# V5_9aSMD.net
KiCad netlist of a schematic drawn in EAGLE
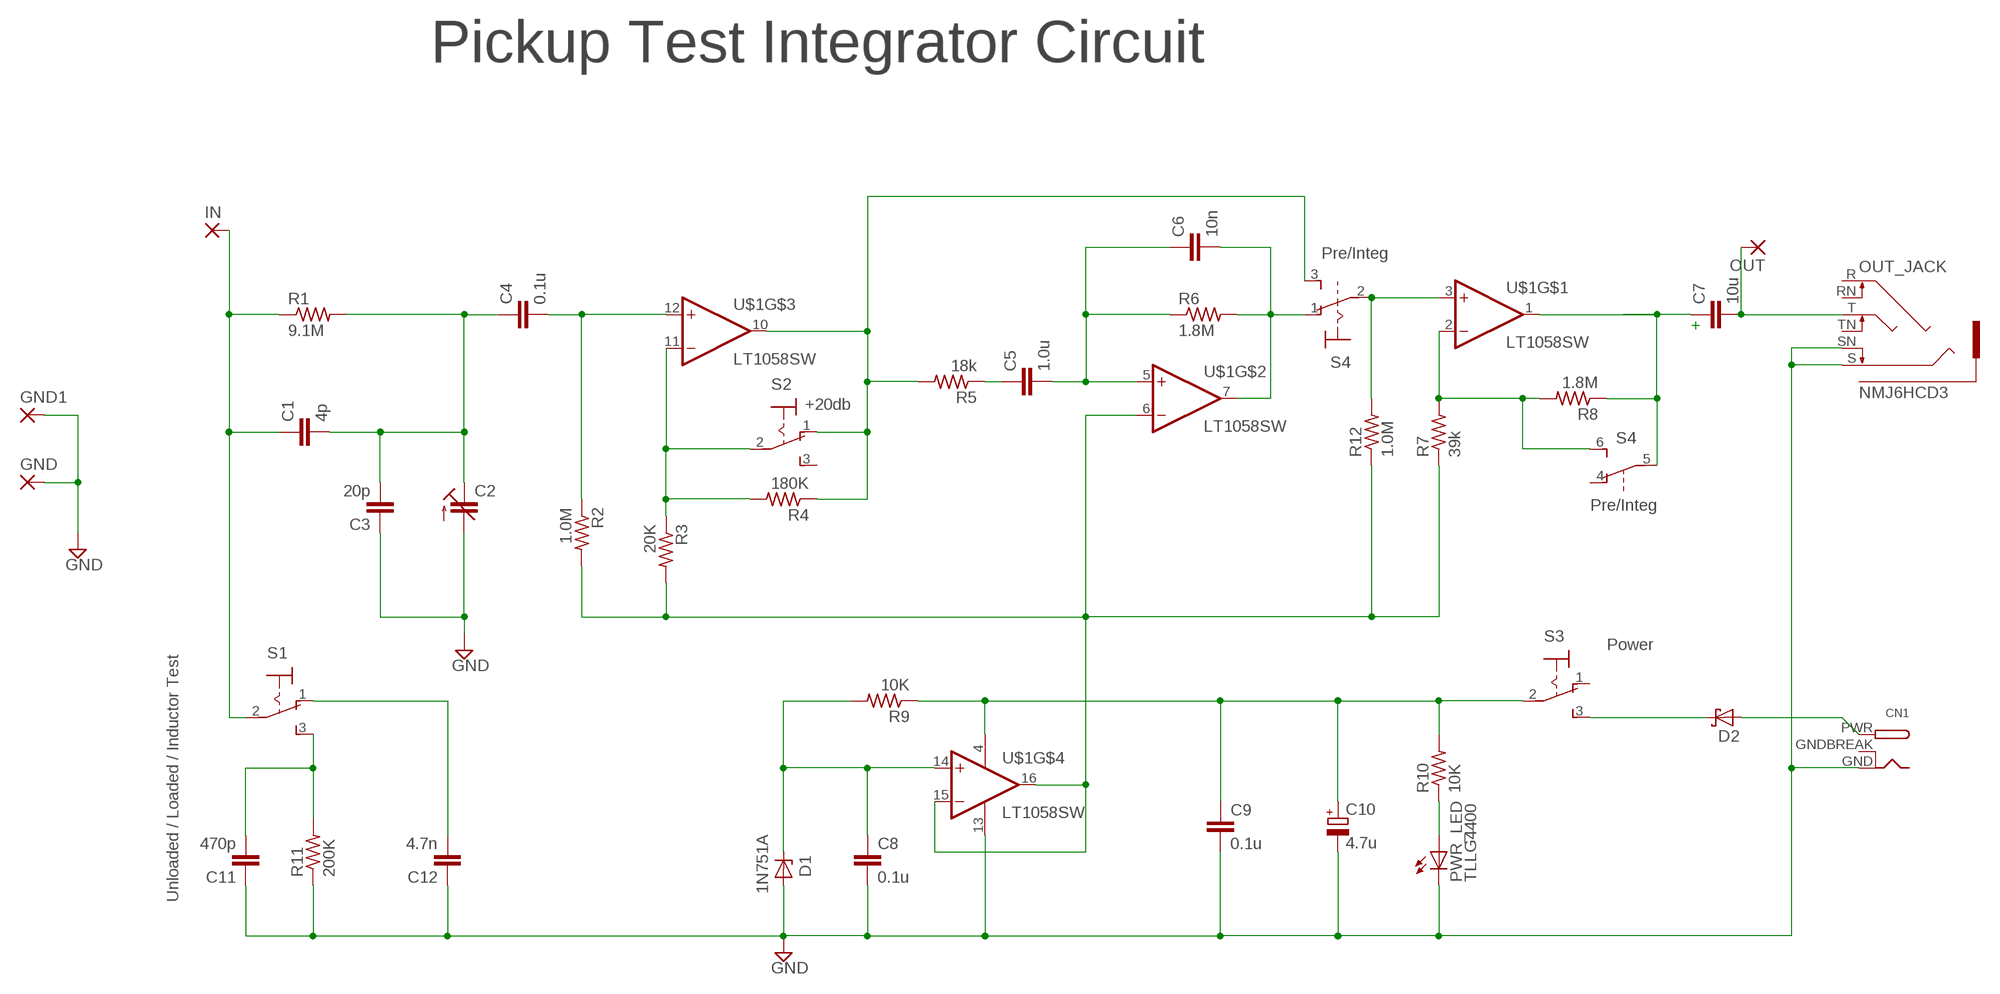
[diagram p0: schematic, sheet 1]

(export (version "E")
  (design (tool "Eeschema 10.0.6"))
  (components
    (comp (ref "C1")
      (value "4p")
      (footprint "eagle-import:C0805")
      (libsource (lib "eagle-import") (part "C-EUC0805"))
    )
    (comp (ref "C2")
      (value "C-TRIMMGKG20015")
      (footprint "eagle-import:GKG20015")
      (libsource (lib "eagle-import") (part "C-TRIMMGKG20015"))
    )
    (comp (ref "C3")
      (value "20p")
      (footprint "eagle-import:C0805")
      (libsource (lib "eagle-import") (part "C-EUC0805"))
    )
    (comp (ref "C4")
      (value "0.1u")
      (footprint "eagle-import:C0805")
      (libsource (lib "eagle-import") (part "C-EUC0805"))
    )
    (comp (ref "C5")
      (value "1.0u")
      (footprint "eagle-import:C0805")
      (libsource (lib "eagle-import") (part "C-EUC0805"))
    )
    (comp (ref "C6")
      (value "10n")
      (footprint "eagle-import:C0805")
      (libsource (lib "eagle-import") (part "C-EUC0805"))
    )
    (comp (ref "C7")
      (value "10u")
      (footprint "eagle-import:C1206K")
      (libsource (lib "eagle-import") (part "C-EUC1206K"))
    )
    (comp (ref "C8")
      (value "0.1u")
      (footprint "eagle-import:C0805")
      (libsource (lib "eagle-import") (part "C-EUC0805"))
    )
    (comp (ref "C9")
      (value "0.1u")
      (footprint "eagle-import:C0805")
      (libsource (lib "eagle-import") (part "C-EUC0805"))
    )
    (comp (ref "C10")
      (value "4.7u")
      (footprint "eagle-import:A_3216-18R")
      (libsource (lib "eagle-import") (part "CPOL-EUA/3216-18R"))
    )
    (comp (ref "C11")
      (value "470p")
      (footprint "eagle-import:C0805")
      (libsource (lib "eagle-import") (part "C-EUC0805"))
    )
    (comp (ref "C12")
      (value "4.7n")
      (footprint "eagle-import:C0805")
      (libsource (lib "eagle-import") (part "C-EUC0805"))
    )
    (comp (ref "CN1")
      (value "DCBARRELPTH")
      (footprint "eagle-import:DCJACK_2MM_PTH")
      (libsource (lib "eagle-import") (part "DCBARRELPTH"))
    )
    (comp (ref "D1")
      (value "ZENER-DIODESOD80C")
      (footprint "eagle-import:SOD80C")
      (libsource (lib "eagle-import") (part "ZENER-DIODESOD80C"))
    )
    (comp (ref "D2")
      (value "SCHOTTKY-DIODESMD")
      (footprint "eagle-import:SMB")
      (libsource (lib "eagle-import") (part "SCHOTTKY-DIODESMD"))
    )
    (comp (ref "GND")
      (value "2,54/1,1")
      (footprint "eagle-import:2,54_1,1")
      (libsource (lib "eagle-import") (part "2,54/1,1"))
    )
    (comp (ref "GND1")
      (value "2,54/1,1")
      (footprint "eagle-import:2,54_1,1")
      (libsource (lib "eagle-import") (part "2,54/1,1"))
    )
    (comp (ref "IN")
      (value "2,54/1,1")
      (footprint "eagle-import:2,54_1,1")
      (libsource (lib "eagle-import") (part "2,54/1,1"))
    )
    (comp (ref "OUT")
      (value "2,54/1,1")
      (footprint "eagle-import:2,54_1,1")
      (libsource (lib "eagle-import") (part "2,54/1,1"))
    )
    (comp (ref "OUT_JACK")
      (value "NMJ6HCD3")
      (footprint "eagle-import:AUDIO_JACK_NEUTRIK")
      (libsource (lib "eagle-import") (part "NMJ6HCD3"))
    )
    (comp (ref "PWR_LED")
      (value "TLLG4400")
      (footprint "eagle-import:LED3MM")
      (fields (field (name "MF") "VISHAY SEMICONDUCTOR"))
      (libsource (lib "eagle-import") (part "TLLG4400"))
    )
    (comp (ref "R1")
      (value "9.1M")
      (footprint "eagle-import:R0805")
      (libsource (lib "eagle-import") (part "R-US_R0805"))
    )
    (comp (ref "R2")
      (value "1.0M")
      (footprint "eagle-import:R0805")
      (libsource (lib "eagle-import") (part "R-US_R0805"))
    )
    (comp (ref "R3")
      (value "20K")
      (footprint "eagle-import:R0805")
      (libsource (lib "eagle-import") (part "R-US_R0805"))
    )
    (comp (ref "R4")
      (value "180K")
      (footprint "eagle-import:R0805")
      (libsource (lib "eagle-import") (part "R-US_R0805"))
    )
    (comp (ref "R5")
      (value "18k")
      (footprint "eagle-import:R0805")
      (libsource (lib "eagle-import") (part "R-US_R0805"))
    )
    (comp (ref "R6")
      (value "1.8M")
      (footprint "eagle-import:R0805")
      (libsource (lib "eagle-import") (part "R-US_R0805"))
    )
    (comp (ref "R7")
      (value "39k")
      (footprint "eagle-import:R0805")
      (libsource (lib "eagle-import") (part "R-US_R0805"))
    )
    (comp (ref "R8")
      (value "1.8M")
      (footprint "eagle-import:R0805")
      (libsource (lib "eagle-import") (part "R-US_R0805"))
    )
    (comp (ref "R9")
      (value "10K")
      (footprint "eagle-import:R0805")
      (libsource (lib "eagle-import") (part "R-US_R0805"))
    )
    (comp (ref "R10")
      (value "10K")
      (footprint "eagle-import:R0805")
      (libsource (lib "eagle-import") (part "R-US_R0805"))
    )
    (comp (ref "R11")
      (value "200K")
      (footprint "eagle-import:R0805")
      (libsource (lib "eagle-import") (part "R-US_R0805"))
    )
    (comp (ref "R12")
      (value "1.0M")
      (footprint "eagle-import:R0805")
      (libsource (lib "eagle-import") (part "R-US_R0805"))
    )
    (comp (ref "S1")
      (value "320-916")
      (footprint "eagle-import:320-916")
      (libsource (lib "eagle-import") (part "320-916"))
    )
    (comp (ref "S2")
      (value "320-916")
      (footprint "eagle-import:320-916")
      (libsource (lib "eagle-import") (part "320-916"))
    )
    (comp (ref "S3")
      (value "320-916")
      (footprint "eagle-import:320-916")
      (libsource (lib "eagle-import") (part "320-916"))
    )
    (comp (ref "S4")
      (value "320-938")
      (footprint "eagle-import:320-938")
      (libsource (lib "eagle-import") (part "320-938"))
    )
    (comp (ref "U$1")
      (value "LT1058SW")
      (footprint "eagle-import:SO16W")
      (libsource (lib "eagle-import") (part "LT1058SW"))
    )
  )
  (nets
    (net (code "1") (name "/GNDBREAK") (class "Default")
      (node (ref "CN1") (pin "GNDBREAK") (pinfunction "GNDBREAK_GNDBREAK") (pintype "power_in"))
    )
    (net (code "2") (name "GND") (class "Default")
      (node (ref "C10") (pin "-") (pinfunction "-_-") (pintype "passive"))
      (node (ref "C11") (pin "1") (pinfunction "1_1") (pintype "passive"))
      (node (ref "C12") (pin "1") (pinfunction "1_1") (pintype "passive"))
      (node (ref "C2") (pin "1") (pinfunction "A_1") (pintype "passive"))
      (node (ref "C3") (pin "1") (pinfunction "1_1") (pintype "passive"))
      (node (ref "C8") (pin "2") (pinfunction "2_2") (pintype "passive"))
      (node (ref "C9") (pin "2") (pinfunction "2_2") (pintype "passive"))
      (node (ref "CN1") (pin "GND") (pinfunction "GND_GND") (pintype "power_in"))
      (node (ref "D1") (pin "A") (pinfunction "A_A") (pintype "passive"))
      (node (ref "GND") (pin "1") (pinfunction "P_1") (pintype "passive"))
      (node (ref "GND1") (pin "1") (pinfunction "P_1") (pintype "passive"))
      (node (ref "OUT_JACK") (pin "S") (pinfunction "S_S") (pintype "passive"))
      (node (ref "OUT_JACK") (pin "SN") (pinfunction "SN_SN") (pintype "passive"))
      (node (ref "PWR_LED") (pin "K") (pinfunction "C_K") (pintype "passive"))
      (node (ref "R11") (pin "1") (pinfunction "1_1") (pintype "passive"))
      (node (ref "U$1") (pin "13") (pinfunction "V-_13") (pintype "power_in"))
    )
    (net (code "3") (name "Net-(C2-E)") (class "Default")
      (node (ref "C1") (pin "2") (pinfunction "2_2") (pintype "passive"))
      (node (ref "C2") (pin "2") (pinfunction "E_2") (pintype "passive"))
      (node (ref "C3") (pin "2") (pinfunction "2_2") (pintype "passive"))
      (node (ref "C4") (pin "1") (pinfunction "1_1") (pintype "passive"))
      (node (ref "R1") (pin "2") (pinfunction "2_2") (pintype "passive"))
    )
    (net (code "4") (name "Net-(C5-Pad1)") (class "Default")
      (node (ref "C5") (pin "1") (pinfunction "1_1") (pintype "passive"))
      (node (ref "R5") (pin "1") (pinfunction "1_1") (pintype "passive"))
    )
    (net (code "5") (name "Net-(CN1-PadPWR)") (class "Default")
      (node (ref "CN1") (pin "PWR") (pinfunction "PWR_PWR") (pintype "power_in"))
      (node (ref "D2") (pin "A") (pinfunction "A_A") (pintype "passive"))
    )
    (net (code "6") (name "Net-(IN-P)") (class "Default")
      (node (ref "C1") (pin "1") (pinfunction "1_1") (pintype "passive"))
      (node (ref "IN") (pin "1") (pinfunction "P_1") (pintype "passive"))
      (node (ref "R1") (pin "1") (pinfunction "1_1") (pintype "passive"))
      (node (ref "S1") (pin "2") (pinfunction "P_2") (pintype "passive"))
    )
    (net (code "7") (name "Net-(OUT-P)") (class "Default")
      (node (ref "C7") (pin "2") (pinfunction "2_2") (pintype "passive"))
      (node (ref "OUT") (pin "1") (pinfunction "P_1") (pintype "passive"))
      (node (ref "OUT_JACK") (pin "T") (pinfunction "T_T") (pintype "passive"))
    )
    (net (code "8") (name "Net-(PWR_LED-PadA)") (class "Default")
      (node (ref "PWR_LED") (pin "A") (pinfunction "A_A") (pintype "passive"))
      (node (ref "R10") (pin "1") (pinfunction "1_1") (pintype "passive"))
    )
    (net (code "9") (name "Net-(S1-O)") (class "Default")
      (node (ref "C12") (pin "2") (pinfunction "2_2") (pintype "passive"))
      (node (ref "S1") (pin "1") (pinfunction "O_1") (pintype "passive"))
    )
    (net (code "10") (name "Net-(S1-S)") (class "Default")
      (node (ref "C11") (pin "2") (pinfunction "2_2") (pintype "passive"))
      (node (ref "R11") (pin "2") (pinfunction "2_2") (pintype "passive"))
      (node (ref "S1") (pin "3") (pinfunction "S_3") (pintype "passive"))
    )
    (net (code "11") (name "Net-(S2-O)") (class "Default")
      (node (ref "R4") (pin "1") (pinfunction "1_1") (pintype "passive"))
      (node (ref "R5") (pin "2") (pinfunction "2_2") (pintype "passive"))
      (node (ref "S2") (pin "1") (pinfunction "O_1") (pintype "passive"))
      (node (ref "S4") (pin "3") (pinfunction "S_3") (pintype "passive"))
      (node (ref "U$1") (pin "10") (pinfunction "OUT_10") (pintype "output"))
    )
    (net (code "12") (name "Net-(S2-P)") (class "Default")
      (node (ref "R3") (pin "1") (pinfunction "1_1") (pintype "passive"))
      (node (ref "R4") (pin "2") (pinfunction "2_2") (pintype "passive"))
      (node (ref "S2") (pin "2") (pinfunction "P_2") (pintype "passive"))
      (node (ref "U$1") (pin "11") (pinfunction "-IN_11") (pintype "input"))
    )
    (net (code "13") (name "Net-(S3-P)") (class "Default")
      (node (ref "C10") (pin "+") (pinfunction "+_+") (pintype "passive"))
      (node (ref "C9") (pin "1") (pinfunction "1_1") (pintype "passive"))
      (node (ref "R10") (pin "2") (pinfunction "2_2") (pintype "passive"))
      (node (ref "R9") (pin "1") (pinfunction "1_1") (pintype "passive"))
      (node (ref "S3") (pin "2") (pinfunction "P_2") (pintype "passive"))
      (node (ref "U$1") (pin "4") (pinfunction "V+_4") (pintype "power_in"))
    )
    (net (code "14") (name "Net-(S3-S)") (class "Default")
      (node (ref "D2") (pin "C") (pinfunction "C_C") (pintype "passive"))
      (node (ref "S3") (pin "3") (pinfunction "S_3") (pintype "passive"))
    )
    (net (code "15") (name "Net-(S4A-O)") (class "Default")
      (node (ref "C6") (pin "2") (pinfunction "2_2") (pintype "passive"))
      (node (ref "R6") (pin "2") (pinfunction "2_2") (pintype "passive"))
      (node (ref "S4") (pin "1") (pinfunction "O_1") (pintype "passive"))
      (node (ref "U$1") (pin "7") (pinfunction "OUT_7") (pintype "output"))
    )
    (net (code "16") (name "Net-(S4A-P)") (class "Default")
      (node (ref "R12") (pin "2") (pinfunction "2_2") (pintype "passive"))
      (node (ref "S4") (pin "2") (pinfunction "P_2") (pintype "passive"))
      (node (ref "U$1") (pin "3") (pinfunction "+IN_3") (pintype "input"))
    )
    (net (code "17") (name "Net-(S4B-P)") (class "Default")
      (node (ref "C7") (pin "1") (pinfunction "1_1") (pintype "passive"))
      (node (ref "R8") (pin "1") (pinfunction "1_1") (pintype "passive"))
      (node (ref "S4") (pin "5") (pinfunction "P_5") (pintype "passive"))
      (node (ref "U$1") (pin "1") (pinfunction "OUT_1") (pintype "output"))
    )
    (net (code "18") (name "Net-(S4B-S)") (class "Default")
      (node (ref "R7") (pin "2") (pinfunction "2_2") (pintype "passive"))
      (node (ref "R8") (pin "2") (pinfunction "2_2") (pintype "passive"))
      (node (ref "S4") (pin "6") (pinfunction "S_6") (pintype "passive"))
      (node (ref "U$1") (pin "2") (pinfunction "-IN_2") (pintype "input"))
    )
    (net (code "19") (name "Net-(U$1B-+IN)") (class "Default")
      (node (ref "C5") (pin "2") (pinfunction "2_2") (pintype "passive"))
      (node (ref "C6") (pin "1") (pinfunction "1_1") (pintype "passive"))
      (node (ref "R6") (pin "1") (pinfunction "1_1") (pintype "passive"))
      (node (ref "U$1") (pin "5") (pinfunction "+IN_5") (pintype "input"))
    )
    (net (code "20") (name "Net-(U$1B--IN)") (class "Default")
      (node (ref "R12") (pin "1") (pinfunction "1_1") (pintype "passive"))
      (node (ref "R2") (pin "2") (pinfunction "2_2") (pintype "passive"))
      (node (ref "R3") (pin "2") (pinfunction "2_2") (pintype "passive"))
      (node (ref "R7") (pin "1") (pinfunction "1_1") (pintype "passive"))
      (node (ref "U$1") (pin "15") (pinfunction "-IN_15") (pintype "input"))
      (node (ref "U$1") (pin "16") (pinfunction "OUT_16") (pintype "output"))
      (node (ref "U$1") (pin "6") (pinfunction "-IN_6") (pintype "input"))
    )
    (net (code "21") (name "Net-(U$1C-+IN)") (class "Default")
      (node (ref "C4") (pin "2") (pinfunction "2_2") (pintype "passive"))
      (node (ref "R2") (pin "1") (pinfunction "1_1") (pintype "passive"))
      (node (ref "U$1") (pin "12") (pinfunction "+IN_12") (pintype "input"))
    )
    (net (code "22") (name "Net-(U$1D-+IN)") (class "Default")
      (node (ref "C8") (pin "1") (pinfunction "1_1") (pintype "passive"))
      (node (ref "D1") (pin "C") (pinfunction "C_C") (pintype "passive"))
      (node (ref "R9") (pin "2") (pinfunction "2_2") (pintype "passive"))
      (node (ref "U$1") (pin "14") (pinfunction "+IN_14") (pintype "input"))
    )
    (net (code "23") (name "unconnected-(OUT_JACK-PadR)") (class "Default")
      (node (ref "OUT_JACK") (pin "R") (pinfunction "R_R") (pintype "passive"))
    )
    (net (code "24") (name "unconnected-(OUT_JACK-PadRN)") (class "Default")
      (node (ref "OUT_JACK") (pin "RN") (pinfunction "RN_RN") (pintype "passive"))
    )
    (net (code "25") (name "unconnected-(OUT_JACK-PadTN)") (class "Default")
      (node (ref "OUT_JACK") (pin "TN") (pinfunction "TN_TN") (pintype "passive"))
    )
    (net (code "26") (name "unconnected-(S2-S-Pad3)") (class "Default")
      (node (ref "S2") (pin "3") (pinfunction "S_3") (pintype "passive"))
    )
    (net (code "27") (name "unconnected-(S3-O-Pad1)") (class "Default")
      (node (ref "S3") (pin "1") (pinfunction "O_1") (pintype "passive"))
    )
    (net (code "28") (name "unconnected-(S4B-O-Pad4)") (class "Default")
      (node (ref "S4") (pin "4") (pinfunction "O_4") (pintype "passive"))
    )
  )
)
